# sch.net
KiCad netlist of a schematic drawn in Altium Designer
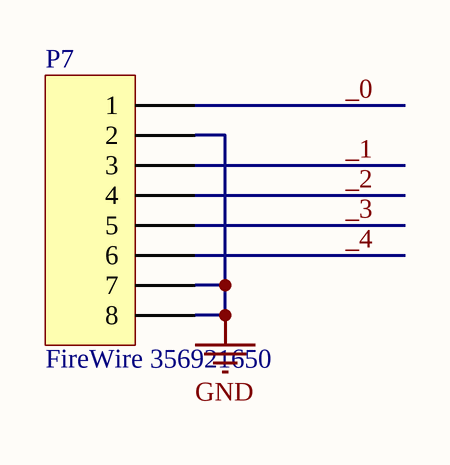
[diagram p0: sch.SchDoc]

(export (version "E")
  (design (tool "Eeschema 10.0.6"))
  (components
    (comp (ref "P7")
      (value "FireWire 356921650")
      (footprint "DS1102")
      (description "IEEE 1394 (DS1102), SMD розетка на плату (OBSOLETE)")
      (fields (field (name "PUBLISHER") "Altium Limited"))
      (libsource (lib "Miscellaneous Connectors") (part "Header 8"))
    )
  )
  (nets
    (net (code "1") (name "/_0") (class "Default")
      (node (ref "P7") (pin "1") (pinfunction "1_1") (pintype "passive"))
    )
    (net (code "2") (name "/_1") (class "Default")
      (node (ref "P7") (pin "3") (pinfunction "3_3") (pintype "passive"))
    )
    (net (code "3") (name "/_2") (class "Default")
      (node (ref "P7") (pin "4") (pinfunction "4_4") (pintype "passive"))
    )
    (net (code "4") (name "/_3") (class "Default")
      (node (ref "P7") (pin "5") (pinfunction "5_5") (pintype "passive"))
    )
    (net (code "5") (name "/_4") (class "Default")
      (node (ref "P7") (pin "6") (pinfunction "6_6") (pintype "passive"))
    )
    (net (code "6") (name "GND") (class "Default")
      (node (ref "P7") (pin "2") (pinfunction "2_2") (pintype "passive"))
      (node (ref "P7") (pin "7") (pinfunction "7_7") (pintype "passive"))
      (node (ref "P7") (pin "8") (pinfunction "8_8") (pintype "passive"))
    )
  )
)
